# batteryholder2S8P.net
KiCad netlist of a schematic drawn in EAGLE
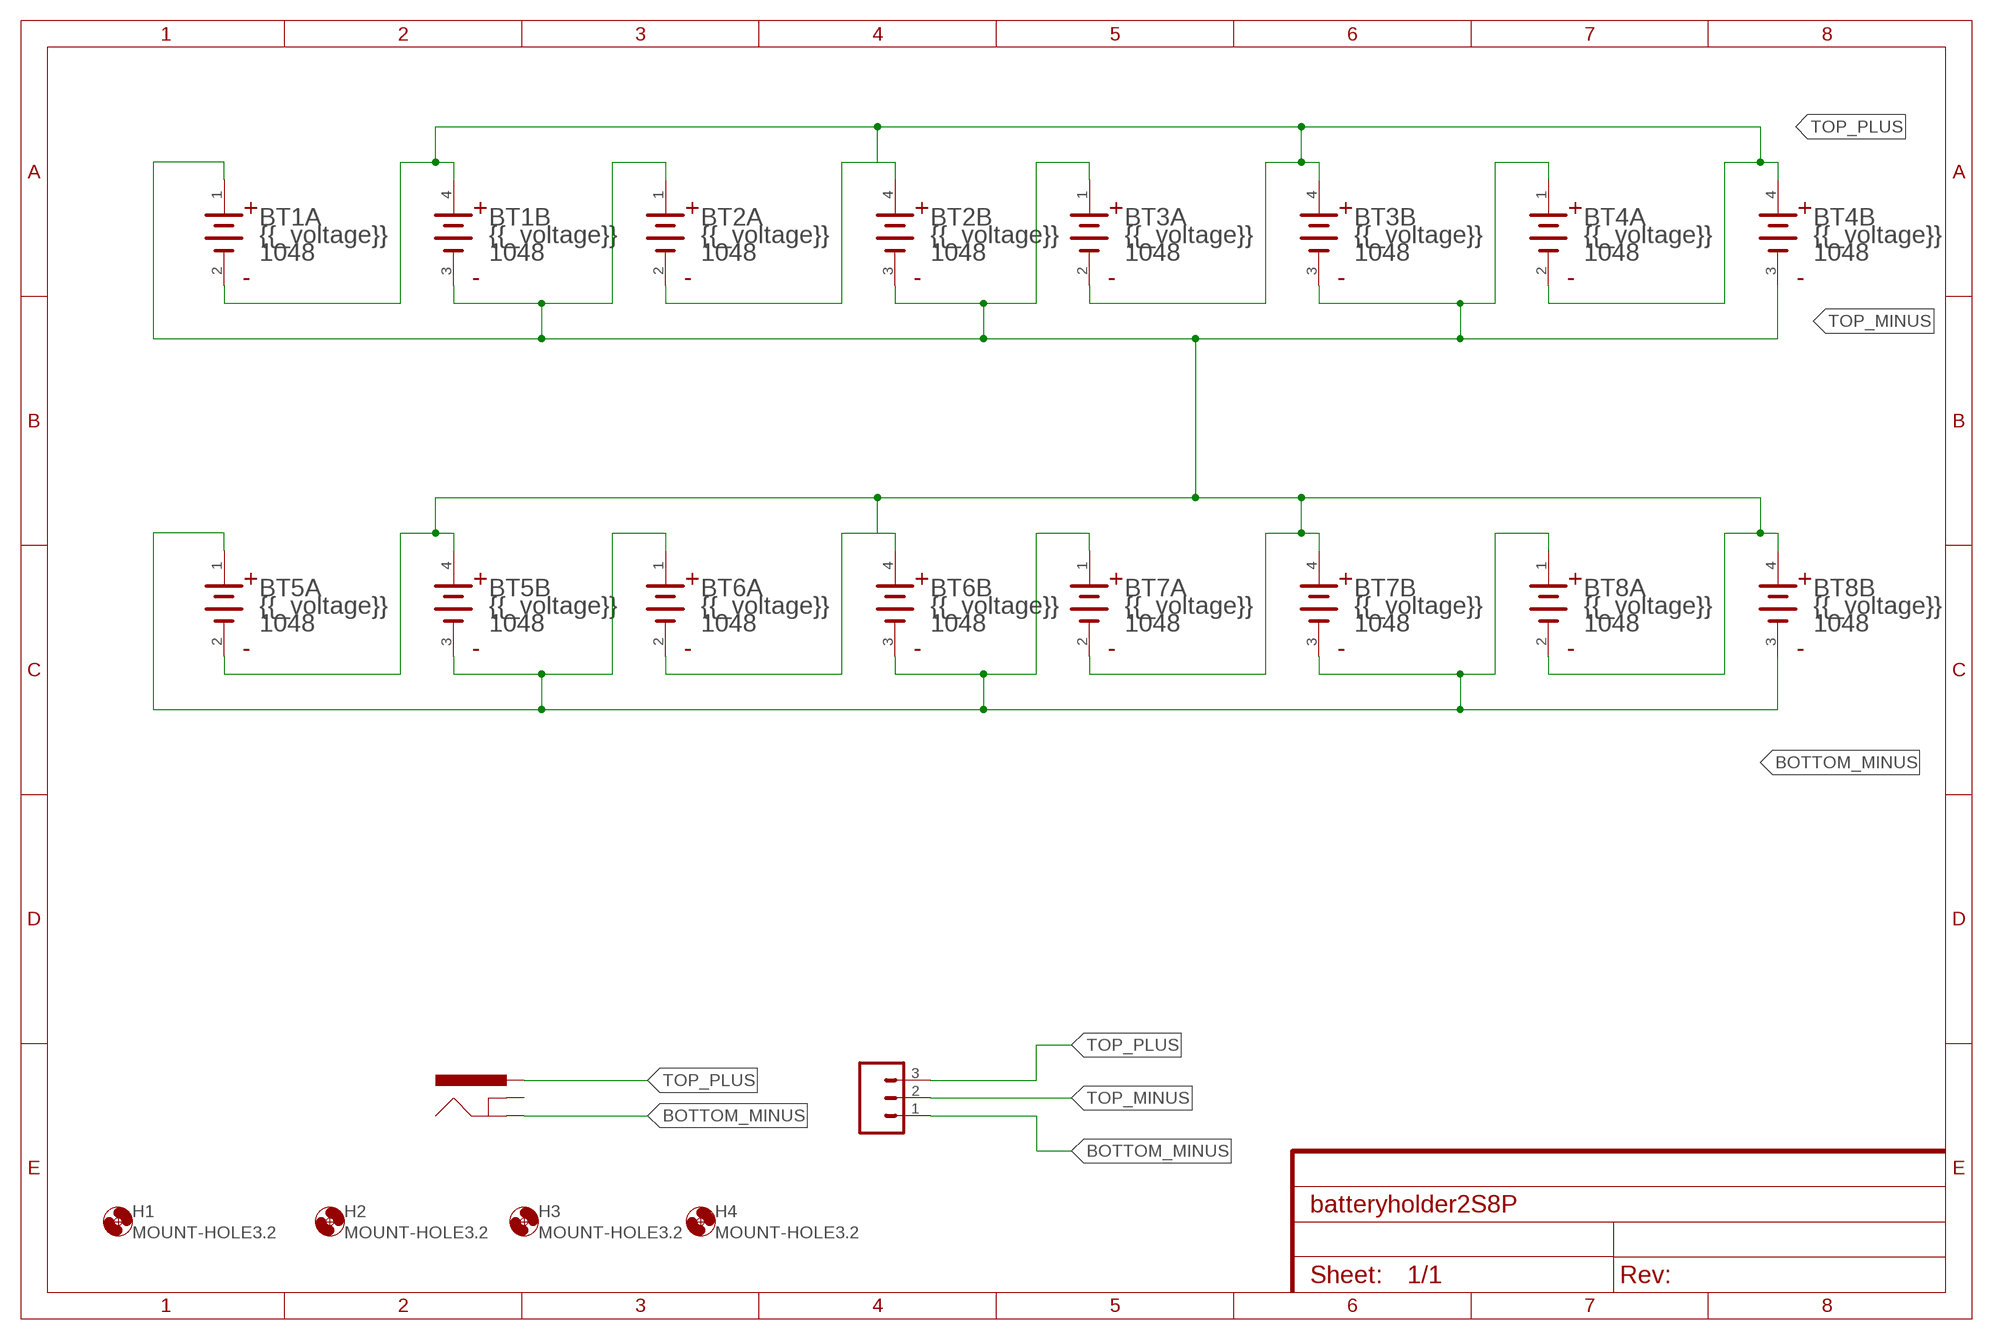
[diagram p0: schematic, sheet 1]

(export (version "E")
  (design (tool "Eeschema 10.0.6"))
  (components
    (comp (ref "BT1")
      (value "KEYSTONE_1048KEYSTONE_1048_0_0")
      (footprint "eagle-import:KEYSTONE_1048_0")
      (fields
        (field (name "DIGIKEY_PART_NUMBER") "36-1048-ND")
        (field (name "MF") "Keystone")
        (field (name "MOUSER_PART_NUMBER") "534-1048")
      )
      (libsource (lib "eagle-import") (part "KEYSTONE_1048KEYSTONE_1048_0_0"))
    )
    (comp (ref "BT2")
      (value "KEYSTONE_1048KEYSTONE_1048_0_0")
      (footprint "eagle-import:KEYSTONE_1048_0")
      (fields
        (field (name "DIGIKEY_PART_NUMBER") "36-1048-ND")
        (field (name "MF") "Keystone")
        (field (name "MOUSER_PART_NUMBER") "534-1048")
      )
      (libsource (lib "eagle-import") (part "KEYSTONE_1048KEYSTONE_1048_0_0"))
    )
    (comp (ref "BT3")
      (value "KEYSTONE_1048KEYSTONE_1048_0_0")
      (footprint "eagle-import:KEYSTONE_1048_0")
      (fields
        (field (name "DIGIKEY_PART_NUMBER") "36-1048-ND")
        (field (name "MF") "Keystone")
        (field (name "MOUSER_PART_NUMBER") "534-1048")
      )
      (libsource (lib "eagle-import") (part "KEYSTONE_1048KEYSTONE_1048_0_0"))
    )
    (comp (ref "BT4")
      (value "KEYSTONE_1048KEYSTONE_1048_0_0")
      (footprint "eagle-import:KEYSTONE_1048_0")
      (fields
        (field (name "DIGIKEY_PART_NUMBER") "36-1048-ND")
        (field (name "MF") "Keystone")
        (field (name "MOUSER_PART_NUMBER") "534-1048")
      )
      (libsource (lib "eagle-import") (part "KEYSTONE_1048KEYSTONE_1048_0_0"))
    )
    (comp (ref "BT5")
      (value "KEYSTONE_1048KEYSTONE_1048_0_0")
      (footprint "eagle-import:KEYSTONE_1048_0")
      (fields
        (field (name "DIGIKEY_PART_NUMBER") "36-1048-ND")
        (field (name "MF") "Keystone")
        (field (name "MOUSER_PART_NUMBER") "534-1048")
      )
      (libsource (lib "eagle-import") (part "KEYSTONE_1048KEYSTONE_1048_0_0"))
    )
    (comp (ref "BT6")
      (value "KEYSTONE_1048KEYSTONE_1048_0_0")
      (footprint "eagle-import:KEYSTONE_1048_0")
      (fields
        (field (name "DIGIKEY_PART_NUMBER") "36-1048-ND")
        (field (name "MF") "Keystone")
        (field (name "MOUSER_PART_NUMBER") "534-1048")
      )
      (libsource (lib "eagle-import") (part "KEYSTONE_1048KEYSTONE_1048_0_0"))
    )
    (comp (ref "BT7")
      (value "KEYSTONE_1048KEYSTONE_1048_0_0")
      (footprint "eagle-import:KEYSTONE_1048_0")
      (fields
        (field (name "DIGIKEY_PART_NUMBER") "36-1048-ND")
        (field (name "MF") "Keystone")
        (field (name "MOUSER_PART_NUMBER") "534-1048")
      )
      (libsource (lib "eagle-import") (part "KEYSTONE_1048KEYSTONE_1048_0_0"))
    )
    (comp (ref "BT8")
      (value "KEYSTONE_1048KEYSTONE_1048_0_0")
      (footprint "eagle-import:KEYSTONE_1048_0")
      (fields
        (field (name "DIGIKEY_PART_NUMBER") "36-1048-ND")
        (field (name "MF") "Keystone")
        (field (name "MOUSER_PART_NUMBER") "534-1048")
      )
      (libsource (lib "eagle-import") (part "KEYSTONE_1048KEYSTONE_1048_0_0"))
    )
    (comp (ref "H1")
      (value "MOUNT-HOLE3.2")
      (footprint "eagle-import:3,2")
      (libsource (lib "eagle-import") (part "MOUNT-HOLE3.2"))
    )
    (comp (ref "H2")
      (value "MOUNT-HOLE3.2")
      (footprint "eagle-import:3,2")
      (libsource (lib "eagle-import") (part "MOUNT-HOLE3.2"))
    )
    (comp (ref "H3")
      (value "MOUNT-HOLE3.2")
      (footprint "eagle-import:3,2")
      (libsource (lib "eagle-import") (part "MOUNT-HOLE3.2"))
    )
    (comp (ref "H4")
      (value "MOUNT-HOLE3.2")
      (footprint "eagle-import:3,2")
      (libsource (lib "eagle-import") (part "MOUNT-HOLE3.2"))
    )
    (comp (ref "J1")
      (value "CONN_03-SCREW-5MM")
      (footprint "eagle-import:SCREWTERMINAL-5MM-3")
      (libsource (lib "eagle-import") (part "CONN_03-SCREW-5MM"))
    )
    (comp (ref "J3")
      (value "POWER_JACKPTH_BREAD")
      (footprint "eagle-import:POWER_JACK_PTH_BREAD")
      (libsource (lib "eagle-import") (part "POWER_JACKPTH_BREAD"))
    )
  )
  (nets
    (net (code "1") (name "BOTTOM_MINUS") (class "Default")
      (node (ref "BT5") (pin "1") (pinfunction "1_ANODE_1") (pintype "passive"))
      (node (ref "BT5") (pin "3") (pinfunction "2_CATHODE_3") (pintype "passive"))
      (node (ref "BT6") (pin "1") (pinfunction "1_ANODE_1") (pintype "passive"))
      (node (ref "BT6") (pin "3") (pinfunction "2_CATHODE_3") (pintype "passive"))
      (node (ref "BT7") (pin "1") (pinfunction "1_ANODE_1") (pintype "passive"))
      (node (ref "BT7") (pin "3") (pinfunction "2_CATHODE_3") (pintype "passive"))
      (node (ref "BT8") (pin "1") (pinfunction "1_ANODE_1") (pintype "passive"))
      (node (ref "BT8") (pin "3") (pinfunction "2_CATHODE_3") (pintype "passive"))
      (node (ref "J1") (pin "1") (pinfunction "1_1") (pintype "passive"))
      (node (ref "J3") (pin "GND") (pinfunction "GND_GND") (pintype "bidirectional"))
    )
    (net (code "2") (name "TOP_MINUS") (class "Default")
      (node (ref "BT1") (pin "1") (pinfunction "1_ANODE_1") (pintype "passive"))
      (node (ref "BT1") (pin "3") (pinfunction "2_CATHODE_3") (pintype "passive"))
      (node (ref "BT2") (pin "1") (pinfunction "1_ANODE_1") (pintype "passive"))
      (node (ref "BT2") (pin "3") (pinfunction "2_CATHODE_3") (pintype "passive"))
      (node (ref "BT3") (pin "1") (pinfunction "1_ANODE_1") (pintype "passive"))
      (node (ref "BT3") (pin "3") (pinfunction "2_CATHODE_3") (pintype "passive"))
      (node (ref "BT4") (pin "1") (pinfunction "1_ANODE_1") (pintype "passive"))
      (node (ref "BT4") (pin "3") (pinfunction "2_CATHODE_3") (pintype "passive"))
      (node (ref "BT5") (pin "2") (pinfunction "1_CATHODE_2") (pintype "passive"))
      (node (ref "BT5") (pin "4") (pinfunction "2_ANODE_4") (pintype "passive"))
      (node (ref "BT6") (pin "2") (pinfunction "1_CATHODE_2") (pintype "passive"))
      (node (ref "BT6") (pin "4") (pinfunction "2_ANODE_4") (pintype "passive"))
      (node (ref "BT7") (pin "2") (pinfunction "1_CATHODE_2") (pintype "passive"))
      (node (ref "BT7") (pin "4") (pinfunction "2_ANODE_4") (pintype "passive"))
      (node (ref "BT8") (pin "2") (pinfunction "1_CATHODE_2") (pintype "passive"))
      (node (ref "BT8") (pin "4") (pinfunction "2_ANODE_4") (pintype "passive"))
      (node (ref "J1") (pin "2") (pinfunction "2_2") (pintype "passive"))
    )
    (net (code "3") (name "TOP_PLUS") (class "Default")
      (node (ref "BT1") (pin "2") (pinfunction "1_CATHODE_2") (pintype "passive"))
      (node (ref "BT1") (pin "4") (pinfunction "2_ANODE_4") (pintype "passive"))
      (node (ref "BT2") (pin "2") (pinfunction "1_CATHODE_2") (pintype "passive"))
      (node (ref "BT2") (pin "4") (pinfunction "2_ANODE_4") (pintype "passive"))
      (node (ref "BT3") (pin "2") (pinfunction "1_CATHODE_2") (pintype "passive"))
      (node (ref "BT3") (pin "4") (pinfunction "2_ANODE_4") (pintype "passive"))
      (node (ref "BT4") (pin "2") (pinfunction "1_CATHODE_2") (pintype "passive"))
      (node (ref "BT4") (pin "4") (pinfunction "2_ANODE_4") (pintype "passive"))
      (node (ref "J1") (pin "3") (pinfunction "3_3") (pintype "passive"))
      (node (ref "J3") (pin "PWR") (pinfunction "PWR_PWR") (pintype "bidirectional"))
    )
    (net (code "4") (name "unconnected-(J3-PadGNDBREAK)") (class "Default")
      (node (ref "J3") (pin "GNDBREAK") (pinfunction "GNDBREAK_GNDBREAK") (pintype "bidirectional"))
    )
  )
)
